# HU_revB.net
KiCad netlist of a schematic drawn in Altium Designer
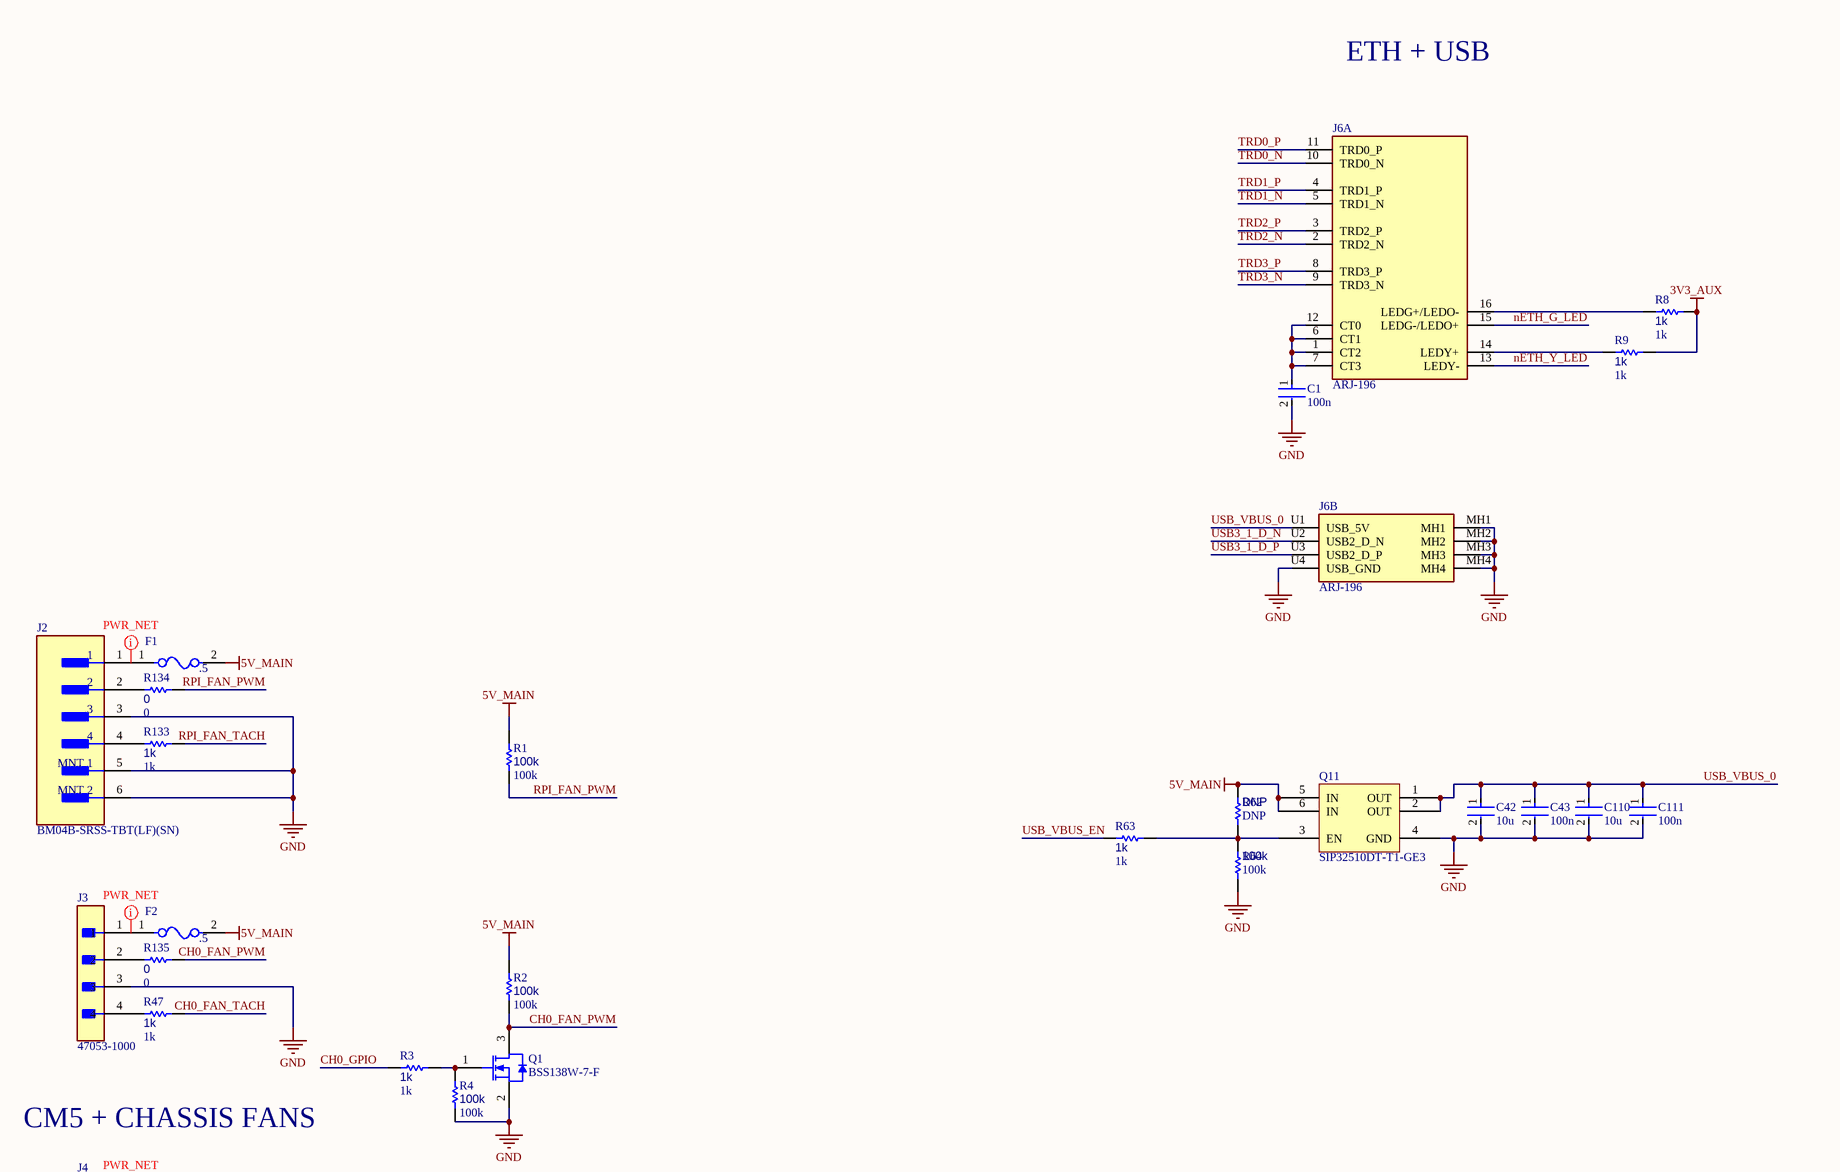
[diagram p0: HU_revB.SchDoc, top right]
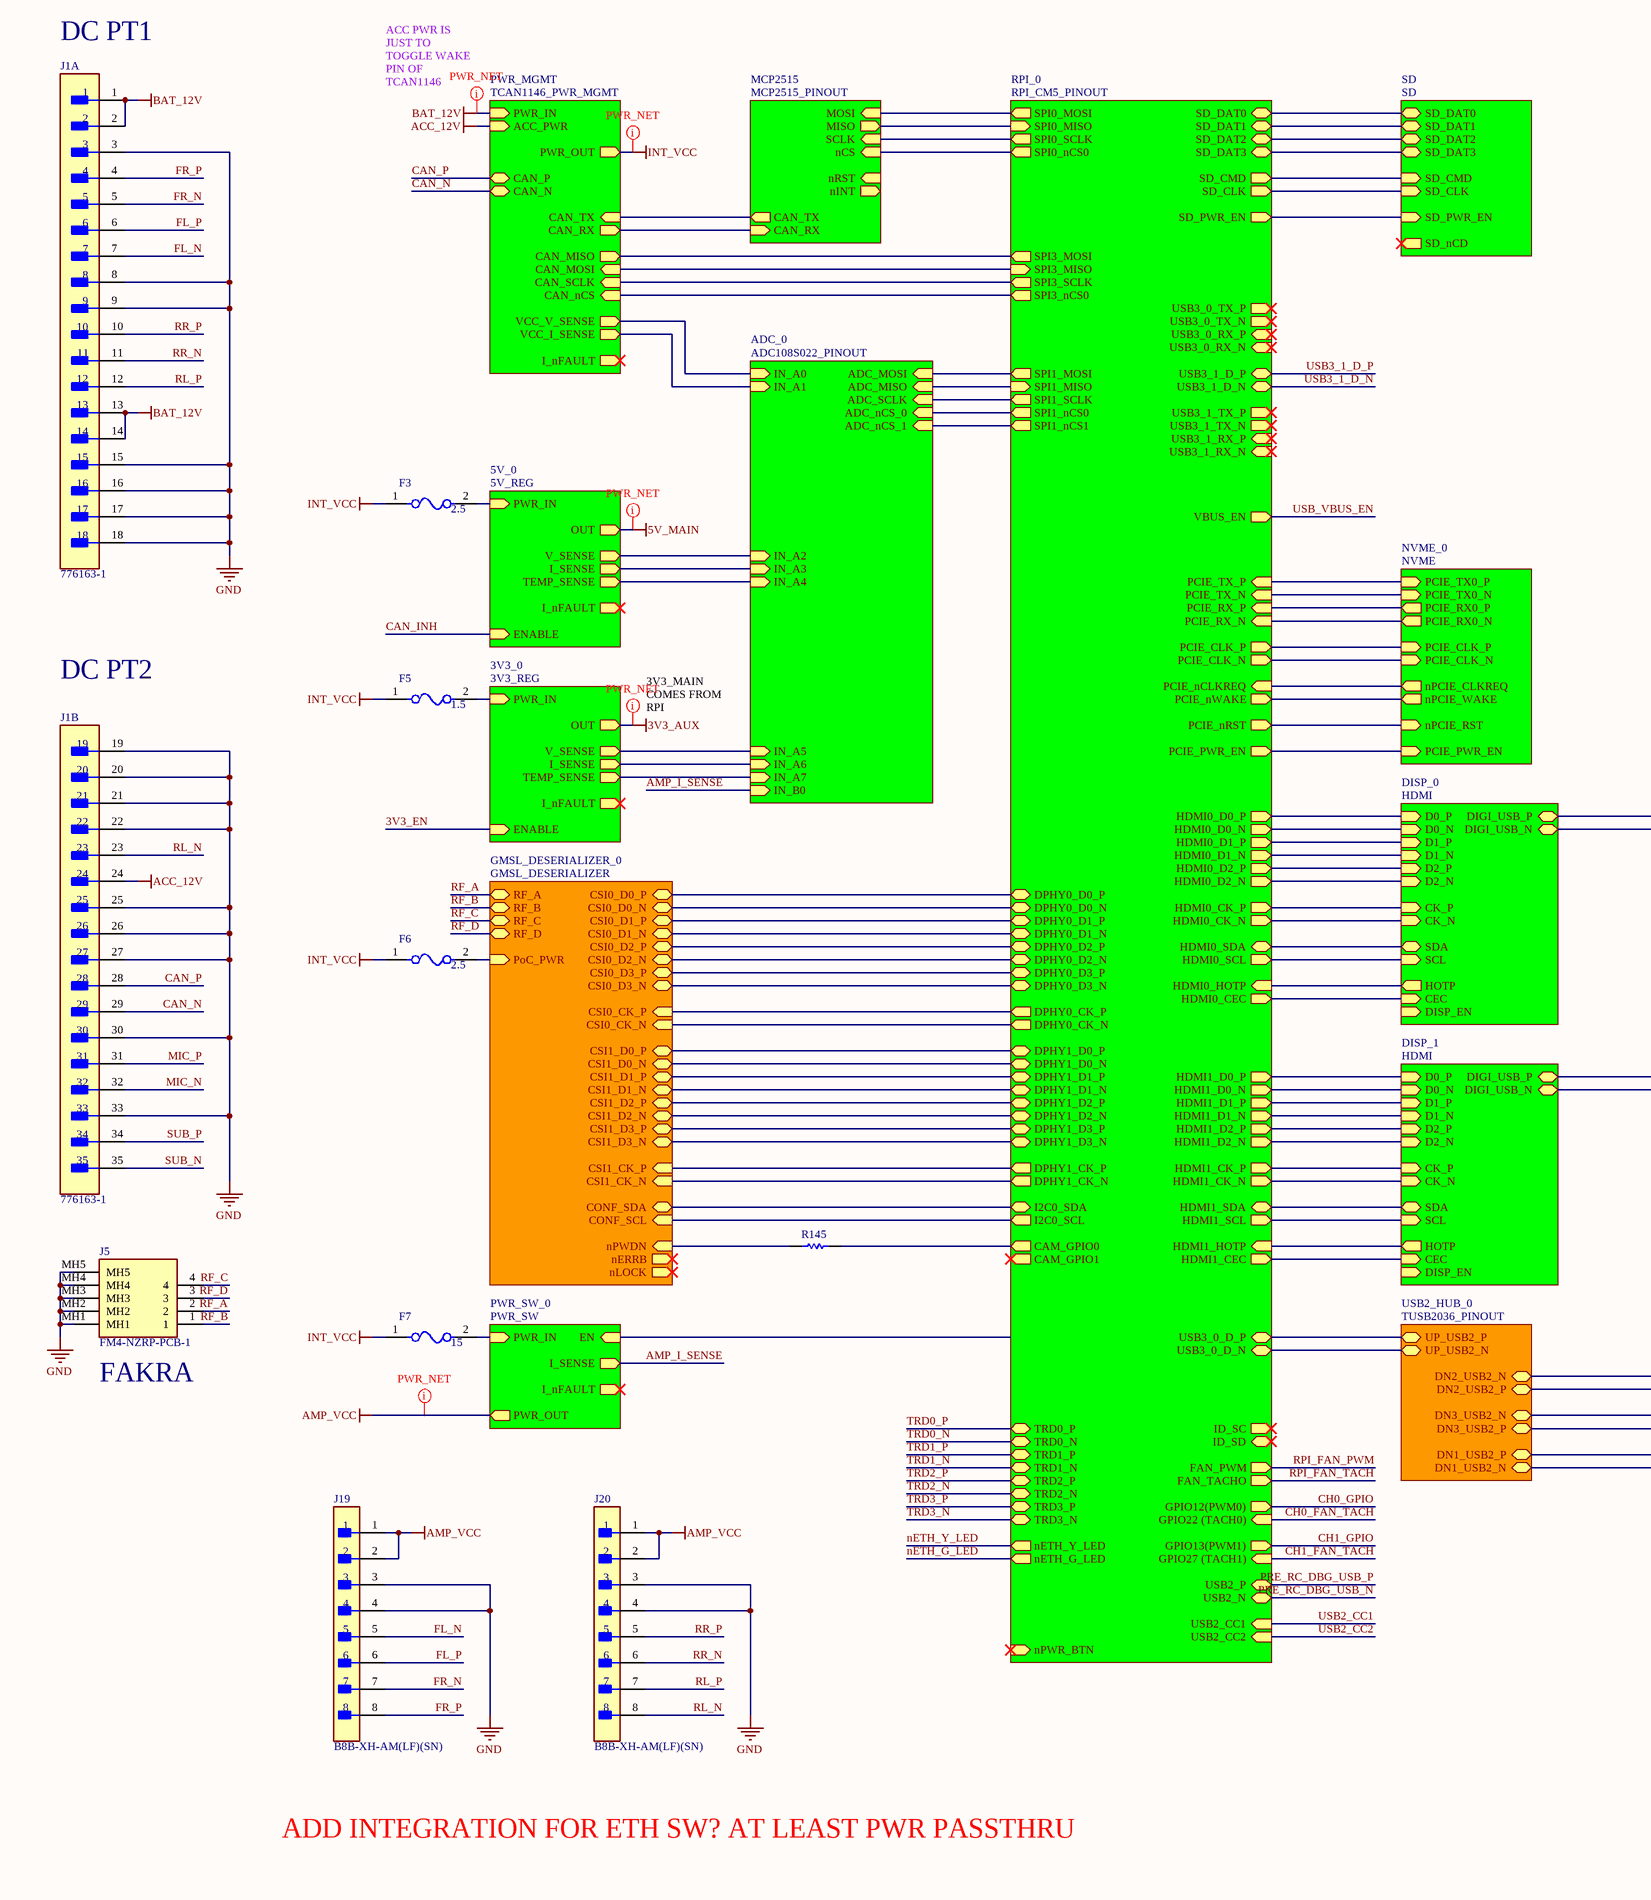
[diagram p1: HU_revB.SchDoc, bottom left]
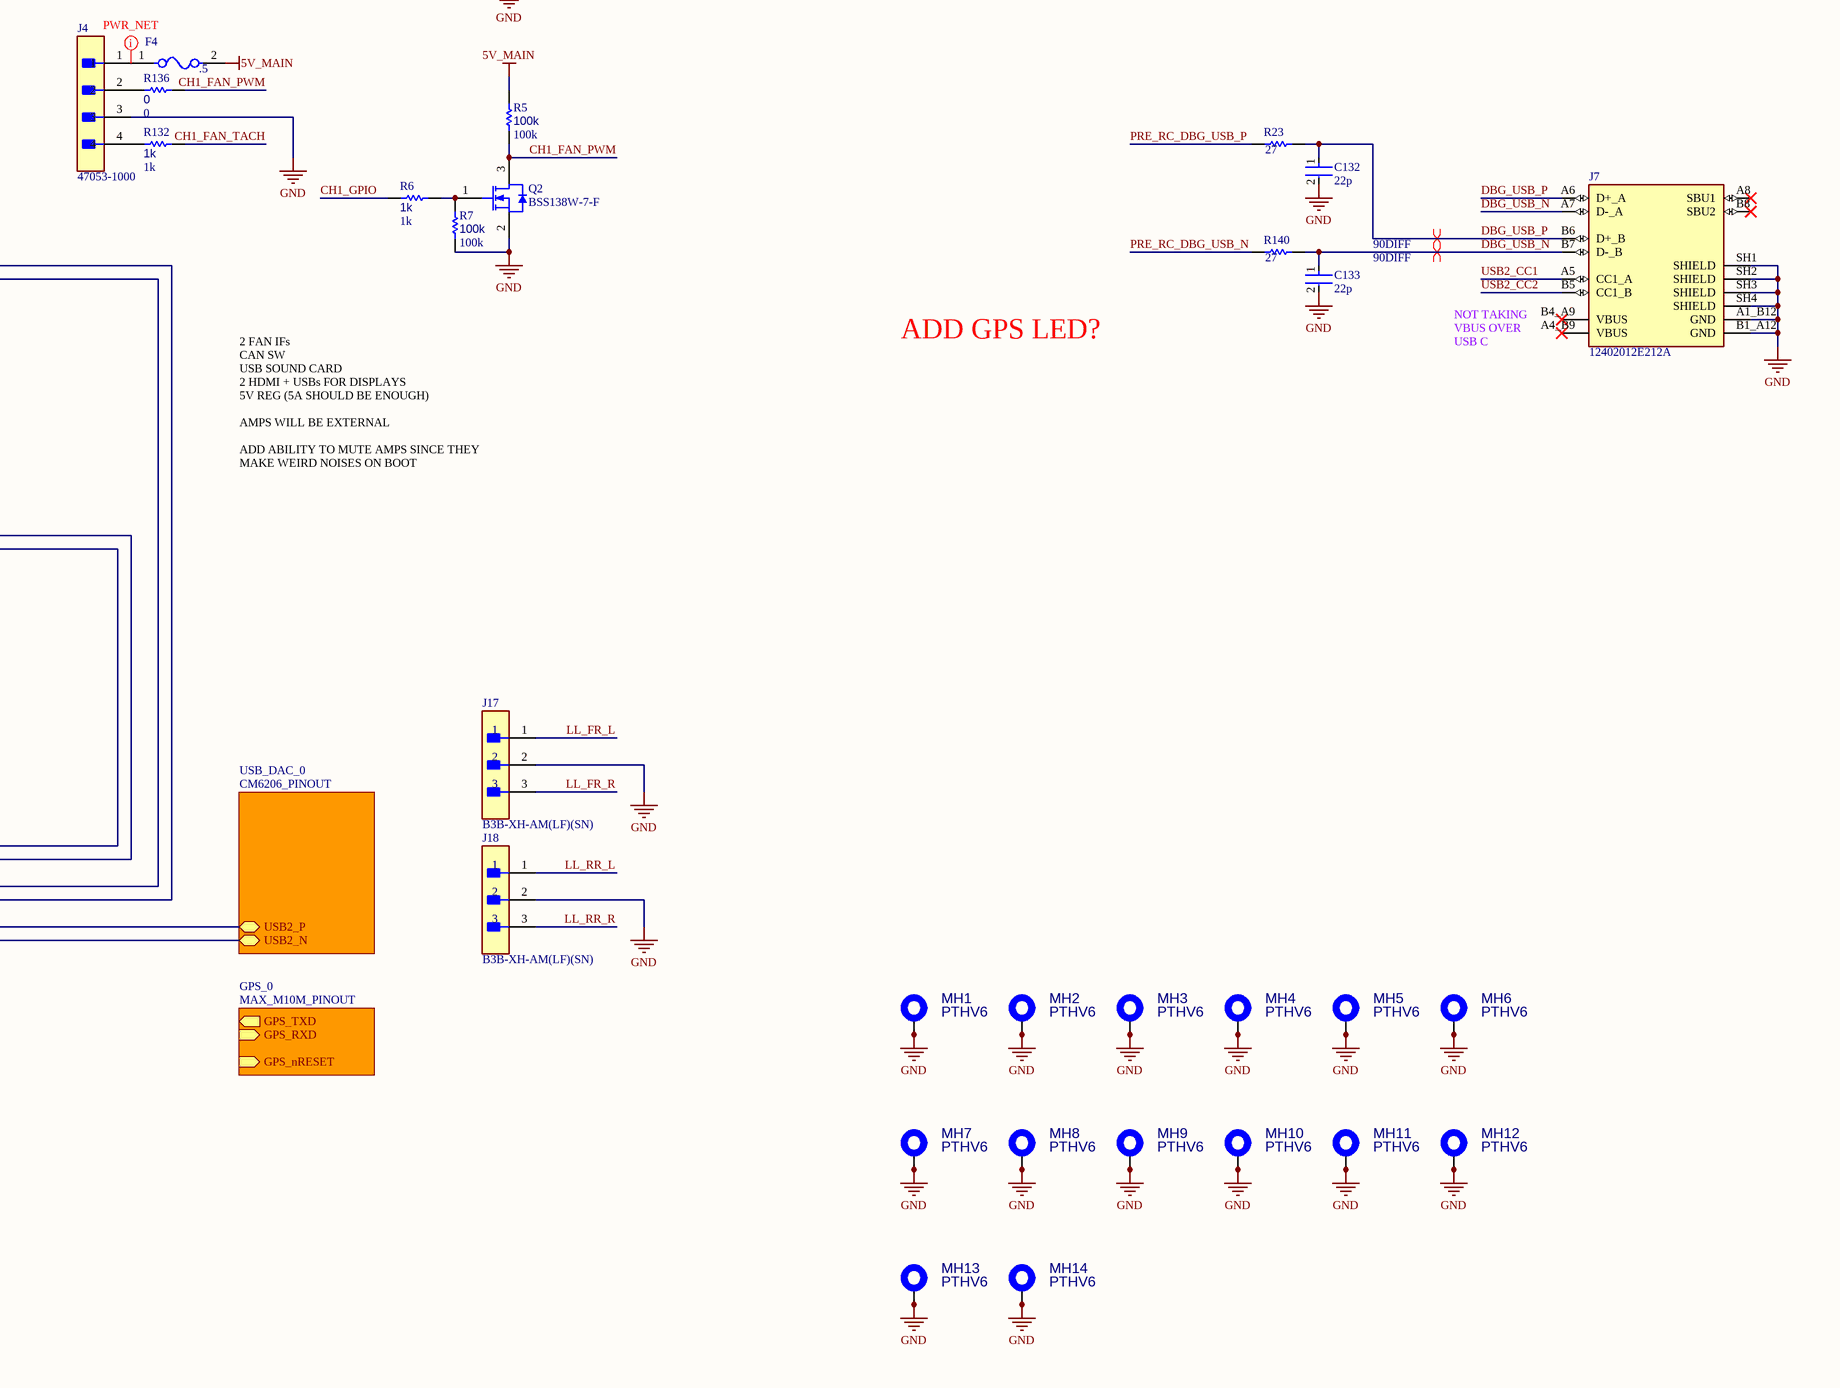
[diagram p2: HU_revB.SchDoc, bottom right]

(export (version "E")
  (design (tool "Eeschema 10.0.6"))
  (components
    (comp (ref "C1")
      (value "100n")
      (footprint "FP-0402-L_1_0_0_05-W_0_5-IPC_A")
      (description "LARGE PADS, 0402 CAP, CHANGE COMMENT TO MATCH REAL P/N")
      (libsource (lib "Space Concordia") (part "b4654b650e69147ec39a6b967a45e02"))
    )
    (comp (ref "C42")
      (value "10u")
      (footprint "FP-0402-L_1_0_0_05-W_0_5-IPC_A")
      (description "LARGE PADS, 0402 CAP, CHANGE COMMENT TO MATCH REAL P/N")
      (libsource (lib "Space Concordia") (part "b4654b650e69147ec39a6b967a45e02"))
    )
    (comp (ref "C43")
      (value "100n")
      (footprint "FP-0402-L_1_0_0_05-W_0_5-IPC_A")
      (description "LARGE PADS, 0402 CAP, CHANGE COMMENT TO MATCH REAL P/N")
      (libsource (lib "Space Concordia") (part "b4654b650e69147ec39a6b967a45e02"))
    )
    (comp (ref "C110")
      (value "10u")
      (footprint "FP-0402-L_1_0_0_05-W_0_5-IPC_A")
      (description "LARGE PADS, 0402 CAP, CHANGE COMMENT TO MATCH REAL P/N")
      (libsource (lib "Space Concordia") (part "b4654b650e69147ec39a6b967a45e02"))
    )
    (comp (ref "C111")
      (value "100n")
      (footprint "FP-0402-L_1_0_0_05-W_0_5-IPC_A")
      (description "LARGE PADS, 0402 CAP, CHANGE COMMENT TO MATCH REAL P/N")
      (libsource (lib "Space Concordia") (part "b4654b650e69147ec39a6b967a45e02"))
    )
    (comp (ref "C132")
      (value "22p")
      (footprint "FP-0402-L_1_0_0_05-W_0_5-IPC_A")
      (description "LARGE PADS, 0402 CAP, CHANGE COMMENT TO MATCH REAL P/N")
      (libsource (lib "Space Concordia") (part "b4654b650e69147ec39a6b967a45e02"))
    )
    (comp (ref "C133")
      (value "22p")
      (footprint "FP-0402-L_1_0_0_05-W_0_5-IPC_A")
      (description "LARGE PADS, 0402 CAP, CHANGE COMMENT TO MATCH REAL P/N")
      (libsource (lib "Space Concordia") (part "b4654b650e69147ec39a6b967a45e02"))
    )
    (comp (ref "F1")
      (value ".5")
      (footprint "FP-0685T-MFG")
      (description "FUSE BOARD MNT 5A 63VAC/VDC 1206")
      (libsource (lib "Altium Content Vault") (part "5bcf9b9f640e542cf0359d10258e979"))
    )
    (comp (ref "F2")
      (value ".5")
      (footprint "FP-0685T-MFG")
      (description "FUSE BOARD MNT 5A 63VAC/VDC 1206")
      (libsource (lib "Altium Content Vault") (part "5bcf9b9f640e542cf0359d10258e979"))
    )
    (comp (ref "F3")
      (value "2.5")
      (footprint "FP-0685T-MFG")
      (description "FUSE BOARD MNT 5A 63VAC/VDC 1206")
      (libsource (lib "Altium Content Vault") (part "5bcf9b9f640e542cf0359d10258e979"))
    )
    (comp (ref "F4")
      (value ".5")
      (footprint "FP-0685T-MFG")
      (description "FUSE BOARD MNT 5A 63VAC/VDC 1206")
      (libsource (lib "Altium Content Vault") (part "5bcf9b9f640e542cf0359d10258e979"))
    )
    (comp (ref "F5")
      (value "1.5")
      (footprint "FP-0685T-MFG")
      (description "FUSE BOARD MNT 5A 63VAC/VDC 1206")
      (libsource (lib "Altium Content Vault") (part "5bcf9b9f640e542cf0359d10258e979"))
    )
    (comp (ref "F6")
      (value "2.5")
      (footprint "FP-0685T-MFG")
      (description "FUSE BOARD MNT 5A 63VAC/VDC 1206")
      (libsource (lib "Altium Content Vault") (part "5bcf9b9f640e542cf0359d10258e979"))
    )
    (comp (ref "F7")
      (value "15")
      (footprint "FP-0685T-MFG")
      (description "FUSE BOARD MNT 5A 63VAC/VDC 1206")
      (libsource (lib "Altium Content Vault") (part "5bcf9b9f640e542cf0359d10258e979"))
    )
    (comp (ref "J1")
      (value "776163-1")
      (footprint "FP-776163-1-MFG")
      (description "CONN HEADER R/A 35POS 4MM")
      (libsource (lib "Altium Content Vault") (part "519b18991870a11d3ebcd8ad3c0113e"))
    )
    (comp (ref "J2")
      (value "BM04B-SRSS-TBT(LF)(SN)")
      (footprint "FP-BM04B-SRSS-TBT_LF_SN-MFG")
      (description "CONN HEADER SMD 4POS 1MM")
      (libsource (lib "Altium Content Vault") (part "8e3688c4b118bffc0dd9b7401e414ba"))
    )
    (comp (ref "J3")
      (value "47053-1000")
      (footprint "FP-470531000-MFG")
      (description "CONN HEADER VERT 4POS 2.54MM")
      (libsource (lib "Altium Content Vault") (part "299a8cea1bdcbc3624fe62c390fa72c"))
    )
    (comp (ref "J4")
      (value "47053-1000")
      (footprint "FP-470531000-MFG")
      (description "CONN HEADER VERT 4POS 2.54MM")
      (libsource (lib "Altium Content Vault") (part "299a8cea1bdcbc3624fe62c390fa72c"))
    )
    (comp (ref "J5")
      (value "FM4-NZRP-PCB-1")
      (footprint "FM4-NZRP-PCB-1-Footprint-1")
      (description "Connector RF Mini-FAKRA Plug 9GHz 50Ohm Solder Right Angle Through Hole")
      (libsource (lib "Space Concordia") (part "CMP-002-00085-1"))
    )
    (comp (ref "J6")
      (value "ARJ-196")
      (footprint "ARJ-196-Footprint-1")
      (description "Modular Connectors / Ethernet Connectors CONN MAGJACK 1PORT 1000 BASE-T")
      (libsource (lib "Space Concordia") (part "ARJ-196"))
    )
    (comp (ref "J7")
      (value "12402012E212A")
      (footprint "12402012E212A-Footprint-1")
      (description "USB Connector, USB Type C, USB 2.0, Receptacle, 24 Ways, Surface Mount, Through Hole Mount")
      (libsource (lib "Space Concordia") (part "12402012E212A"))
    )
    (comp (ref "J17")
      (value "B3B-XH-AM(LF)(SN)")
      (footprint "FP-B3B-XH-AM_LF_SN-MFG")
      (description "CONN HEADER VERT 3POS 2.5MM")
      (libsource (lib "Altium Content Vault") (part "0d3f023dd272f625e17a2be33dea85f"))
    )
    (comp (ref "J18")
      (value "B3B-XH-AM(LF)(SN)")
      (footprint "FP-B3B-XH-AM_LF_SN-MFG")
      (description "CONN HEADER VERT 3POS 2.5MM")
      (libsource (lib "Altium Content Vault") (part "0d3f023dd272f625e17a2be33dea85f"))
    )
    (comp (ref "J19")
      (value "B8B-XH-AM(LF)(SN)")
      (footprint "FP-B8B-XH-AM_LF_SN-MFG")
      (description "CONN HEADER VERT 8POS 2.5MM")
      (libsource (lib "Altium Content Vault") (part "99ec2b232beb5d2356d4d77f6a047f0"))
    )
    (comp (ref "J20")
      (value "B8B-XH-AM(LF)(SN)")
      (footprint "FP-B8B-XH-AM_LF_SN-MFG")
      (description "CONN HEADER VERT 8POS 2.5MM")
      (libsource (lib "Altium Content Vault") (part "99ec2b232beb5d2356d4d77f6a047f0"))
    )
    (comp (ref "MH1")
      (value "PTHV6")
      (footprint "PTHV6 M2")
      (libsource (lib "Space Concordia") (part "PTHV6"))
    )
    (comp (ref "MH2")
      (value "PTHV6")
      (footprint "PTHV6 M2")
      (libsource (lib "Space Concordia") (part "PTHV6"))
    )
    (comp (ref "MH3")
      (value "PTHV6")
      (footprint "PTHV6 M2")
      (libsource (lib "Space Concordia") (part "PTHV6"))
    )
    (comp (ref "MH4")
      (value "PTHV6")
      (footprint "PTHV6 M2")
      (libsource (lib "Space Concordia") (part "PTHV6"))
    )
    (comp (ref "MH5")
      (value "PTHV6")
      (footprint "PTHV6 M2")
      (libsource (lib "Space Concordia") (part "PTHV6"))
    )
    (comp (ref "MH6")
      (value "PTHV6")
      (footprint "PTHV6 M2")
      (libsource (lib "Space Concordia") (part "PTHV6"))
    )
    (comp (ref "MH7")
      (value "PTHV6")
      (footprint "PTHV6 M2")
      (libsource (lib "Space Concordia") (part "PTHV6"))
    )
    (comp (ref "MH8")
      (value "PTHV6")
      (footprint "PTHV6 M2")
      (libsource (lib "Space Concordia") (part "PTHV6"))
    )
    (comp (ref "MH9")
      (value "PTHV6")
      (footprint "PTHV6 M2")
      (libsource (lib "Space Concordia") (part "PTHV6"))
    )
    (comp (ref "MH10")
      (value "PTHV6")
      (footprint "PTHV6 M2")
      (libsource (lib "Space Concordia") (part "PTHV6"))
    )
    (comp (ref "MH11")
      (value "PTHV6")
      (footprint "PTHV6 M2")
      (libsource (lib "Space Concordia") (part "PTHV6"))
    )
    (comp (ref "MH12")
      (value "PTHV6")
      (footprint "PTHV6 M2")
      (libsource (lib "Space Concordia") (part "PTHV6"))
    )
    (comp (ref "MH13")
      (value "PTHV6")
      (footprint "PTHV6 M2")
      (libsource (lib "Space Concordia") (part "PTHV6"))
    )
    (comp (ref "MH14")
      (value "PTHV6")
      (footprint "PTHV6 M2")
      (libsource (lib "Space Concordia") (part "PTHV6"))
    )
    (comp (ref "Q1")
      (value "BSS138W-7-F")
      (footprint "DIOD-SOT323-3_V")
      (fields (field (name "MANUFACTURER") "DiodesIncorporated"))
      (libsource (lib "Altium Content Vault") (part "NEMOS-GSD-3"))
    )
    (comp (ref "Q2")
      (value "BSS138W-7-F")
      (footprint "DIOD-SOT323-3_V")
      (fields (field (name "MANUFACTURER") "DiodesIncorporated"))
      (libsource (lib "Altium Content Vault") (part "NEMOS-GSD-3"))
    )
    (comp (ref "Q11")
      (value "SIP32510DT-T1-GE3")
      (footprint "SOT95P284X110-6N")
      (description "Power Switch ICs – Power Distribution; VISHAY; SIP32510DT-T1-GE3; 1; 1; 5.5 V; SOT-23-6")
      (libsource (lib "Space Concordia") (part "SIP32510DT-T1-GE3"))
    )
    (comp (ref "R1")
      (value "100k")
      (footprint "R0603B")
      (description "Resistor")
      (fields (field (name "ALTIUM_VALUE") "100k"))
      (libsource (lib "Space Concordia") (part "Resistor"))
    )
    (comp (ref "R2")
      (value "100k")
      (footprint "R0603B")
      (description "Resistor")
      (fields (field (name "ALTIUM_VALUE") "100k"))
      (libsource (lib "Space Concordia") (part "Resistor"))
    )
    (comp (ref "R3")
      (value "1k")
      (footprint "R0603B")
      (description "Resistor")
      (fields (field (name "ALTIUM_VALUE") "1k"))
      (libsource (lib "Space Concordia") (part "Resistor"))
    )
    (comp (ref "R4")
      (value "100k")
      (footprint "R0603B")
      (description "Resistor")
      (fields (field (name "ALTIUM_VALUE") "100k"))
      (libsource (lib "Space Concordia") (part "Resistor"))
    )
    (comp (ref "R5")
      (value "100k")
      (footprint "R0603B")
      (description "Resistor")
      (fields (field (name "ALTIUM_VALUE") "100k"))
      (libsource (lib "Space Concordia") (part "Resistor"))
    )
    (comp (ref "R6")
      (value "1k")
      (footprint "R0603B")
      (description "Resistor")
      (fields (field (name "ALTIUM_VALUE") "1k"))
      (libsource (lib "Space Concordia") (part "Resistor"))
    )
    (comp (ref "R7")
      (value "100k")
      (footprint "R0603B")
      (description "Resistor")
      (fields (field (name "ALTIUM_VALUE") "100k"))
      (libsource (lib "Space Concordia") (part "Resistor"))
    )
    (comp (ref "R8")
      (value "1k")
      (footprint "R0603B")
      (description "Resistor")
      (fields (field (name "ALTIUM_VALUE") "1k"))
      (libsource (lib "Space Concordia") (part "Resistor"))
    )
    (comp (ref "R9")
      (value "1k")
      (footprint "R0603B")
      (description "Resistor")
      (fields (field (name "ALTIUM_VALUE") "1k"))
      (libsource (lib "Space Concordia") (part "Resistor"))
    )
    (comp (ref "R23")
      (value "27")
      (footprint "R0603B")
      (description "Resistor")
      (libsource (lib "Space Concordia") (part "Resistor"))
    )
    (comp (ref "R47")
      (value "1k")
      (footprint "R0603B")
      (description "Resistor")
      (fields (field (name "ALTIUM_VALUE") "1k"))
      (libsource (lib "Space Concordia") (part "Resistor"))
    )
    (comp (ref "R62")
      (value "DNP")
      (footprint "R0603B")
      (description "Resistor")
      (fields (field (name "ALTIUM_VALUE") "DNP"))
      (libsource (lib "Space Concordia") (part "Resistor"))
    )
    (comp (ref "R63")
      (value "1k")
      (footprint "R0603B")
      (description "Resistor")
      (fields (field (name "ALTIUM_VALUE") "1k"))
      (libsource (lib "Space Concordia") (part "Resistor"))
    )
    (comp (ref "R64")
      (value "100k")
      (footprint "R0603B")
      (description "Resistor")
      (fields (field (name "ALTIUM_VALUE") "100k"))
      (libsource (lib "Space Concordia") (part "Resistor"))
    )
    (comp (ref "R132")
      (value "1k")
      (footprint "R0603B")
      (description "Resistor")
      (fields (field (name "ALTIUM_VALUE") "1k"))
      (libsource (lib "Space Concordia") (part "Resistor"))
    )
    (comp (ref "R133")
      (value "1k")
      (footprint "R0603B")
      (description "Resistor")
      (fields (field (name "ALTIUM_VALUE") "1k"))
      (libsource (lib "Space Concordia") (part "Resistor"))
    )
    (comp (ref "R134")
      (value "0")
      (footprint "R0603B")
      (description "Resistor")
      (fields (field (name "ALTIUM_VALUE") "0"))
      (libsource (lib "Space Concordia") (part "Resistor"))
    )
    (comp (ref "R135")
      (value "0")
      (footprint "R0603B")
      (description "Resistor")
      (fields (field (name "ALTIUM_VALUE") "0"))
      (libsource (lib "Space Concordia") (part "Resistor"))
    )
    (comp (ref "R136")
      (value "0")
      (footprint "R0603B")
      (description "Resistor")
      (fields (field (name "ALTIUM_VALUE") "0"))
      (libsource (lib "Space Concordia") (part "Resistor"))
    )
    (comp (ref "R140")
      (value "27")
      (footprint "R0603B")
      (description "Resistor")
      (libsource (lib "Space Concordia") (part "Resistor"))
    )
    (comp (ref "R145")
      (value "DNP")
      (footprint "RESC1005X40X25ML05T05")
      (description "READ THE NAME")
      (libsource (lib "Space Concordia") (part "CMP-009-00206-2"))
    )
  )
  (nets
    (net (code "4") (name "/CAM_GPIO0") (class "Default")
      (node (ref "R145") (pin "1") (pinfunction "1_1") (pintype "passive"))
    )
    (net (code "9") (name "/CAN_N") (class "Default")
      (node (ref "J1") (pin "29") (pinfunction "29_29") (pintype "passive"))
    )
    (net (code "10") (name "/CAN_P") (class "Default")
      (node (ref "J1") (pin "28") (pinfunction "28_28") (pintype "passive"))
    )
    (net (code "13") (name "/CH0_FAN_PWM") (class "Default")
      (node (ref "Q1") (pin "3") (pinfunction "D_3") (pintype "passive"))
      (node (ref "R135") (pin "2") (pinfunction "2_2") (pintype "passive"))
      (node (ref "R2") (pin "2") (pinfunction "2_2") (pintype "passive"))
    )
    (net (code "14") (name "/CH0_FAN_TACH") (class "Default")
      (node (ref "R47") (pin "2") (pinfunction "2_2") (pintype "passive"))
    )
    (net (code "15") (name "/CH0_GPIO") (class "Default")
      (node (ref "R3") (pin "1") (pinfunction "1_1") (pintype "passive"))
    )
    (net (code "16") (name "/CH1_FAN_PWM") (class "Default")
      (node (ref "Q2") (pin "3") (pinfunction "D_3") (pintype "passive"))
      (node (ref "R136") (pin "2") (pinfunction "2_2") (pintype "passive"))
      (node (ref "R5") (pin "2") (pinfunction "2_2") (pintype "passive"))
    )
    (net (code "17") (name "/CH1_FAN_TACH") (class "Default")
      (node (ref "R132") (pin "2") (pinfunction "2_2") (pintype "passive"))
    )
    (net (code "18") (name "/CH1_GPIO") (class "Default")
      (node (ref "R6") (pin "1") (pinfunction "1_1") (pintype "passive"))
    )
    (net (code "36") (name "/DBG_USB_N") (class "Default")
      (node (ref "C133") (pin "1") (pinfunction "1_1") (pintype "passive"))
      (node (ref "J7") (pin "A7") (pinfunction "D-_A_A7") (pintype "bidirectional"))
      (node (ref "J7") (pin "B7") (pinfunction "D-_B_B7") (pintype "bidirectional"))
      (node (ref "R140") (pin "1") (pinfunction "1_1") (pintype "passive"))
    )
    (net (code "37") (name "/DBG_USB_P") (class "Default")
      (node (ref "C132") (pin "1") (pinfunction "1_1") (pintype "passive"))
      (node (ref "J7") (pin "A6") (pinfunction "D+_A_A6") (pintype "bidirectional"))
      (node (ref "J7") (pin "B6") (pinfunction "D+_B_B6") (pintype "bidirectional"))
      (node (ref "R23") (pin "1") (pinfunction "1_1") (pintype "passive"))
    )
    (net (code "51") (name "/FL_N") (class "Default")
      (node (ref "J1") (pin "7") (pinfunction "7_7") (pintype "passive"))
      (node (ref "J19") (pin "5") (pinfunction "5_5") (pintype "passive"))
    )
    (net (code "52") (name "/FL_P") (class "Default")
      (node (ref "J1") (pin "6") (pinfunction "6_6") (pintype "passive"))
      (node (ref "J19") (pin "6") (pinfunction "6_6") (pintype "passive"))
    )
    (net (code "53") (name "/FR_N") (class "Default")
      (node (ref "J1") (pin "5") (pinfunction "5_5") (pintype "passive"))
      (node (ref "J19") (pin "7") (pinfunction "7_7") (pintype "passive"))
    )
    (net (code "54") (name "/FR_P") (class "Default")
      (node (ref "J1") (pin "4") (pinfunction "4_4") (pintype "passive"))
      (node (ref "J19") (pin "8") (pinfunction "8_8") (pintype "passive"))
    )
    (net (code "91") (name "/LL_FR_L") (class "Default")
      (node (ref "J17") (pin "1") (pinfunction "1_1") (pintype "passive"))
    )
    (net (code "92") (name "/LL_FR_R") (class "Default")
      (node (ref "J17") (pin "3") (pinfunction "3_3") (pintype "passive"))
    )
    (net (code "93") (name "/LL_RR_L") (class "Default")
      (node (ref "J18") (pin "1") (pinfunction "1_1") (pintype "passive"))
    )
    (net (code "94") (name "/LL_RR_R") (class "Default")
      (node (ref "J18") (pin "3") (pinfunction "3_3") (pintype "passive"))
    )
    (net (code "95") (name "/MIC_N") (class "Default")
      (node (ref "J1") (pin "32") (pinfunction "32_32") (pintype "passive"))
    )
    (net (code "96") (name "/MIC_P") (class "Default")
      (node (ref "J1") (pin "31") (pinfunction "31_31") (pintype "passive"))
    )
    (net (code "107") (name "/PRE_RC_DBG_USB_N") (class "Default")
      (node (ref "R140") (pin "2") (pinfunction "2_2") (pintype "passive"))
    )
    (net (code "108") (name "/PRE_RC_DBG_USB_P") (class "Default")
      (node (ref "R23") (pin "2") (pinfunction "2_2") (pintype "passive"))
    )
    (net (code "109") (name "/PWR_IN") (class "Default")
      (node (ref "F7") (pin "2") (pinfunction "2_2") (pintype "passive"))
    )
    (net (code "110") (name "/PWR_IN_1") (class "Default")
      (node (ref "F3") (pin "2") (pinfunction "2_2") (pintype "passive"))
    )
    (net (code "111") (name "/PWR_IN_2") (class "Default")
      (node (ref "F5") (pin "2") (pinfunction "2_2") (pintype "passive"))
    )
    (net (code "112") (name "/PoC_PWR") (class "Default")
      (node (ref "F6") (pin "2") (pinfunction "2_2") (pintype "passive"))
    )
    (net (code "113") (name "/RF_A") (class "Default")
      (node (ref "J5") (pin "2") (pinfunction "2_2") (pintype "passive"))
    )
    (net (code "114") (name "/RF_B") (class "Default")
      (node (ref "J5") (pin "1") (pinfunction "1_1") (pintype "passive"))
    )
    (net (code "115") (name "/RF_C") (class "Default")
      (node (ref "J5") (pin "4") (pinfunction "4_4") (pintype "passive"))
    )
    (net (code "116") (name "/RF_D") (class "Default")
      (node (ref "J5") (pin "3") (pinfunction "3_3") (pintype "passive"))
    )
    (net (code "117") (name "/RL_N") (class "Default")
      (node (ref "J1") (pin "23") (pinfunction "23_23") (pintype "passive"))
      (node (ref "J20") (pin "8") (pinfunction "8_8") (pintype "passive"))
    )
    (net (code "118") (name "/RL_P") (class "Default")
      (node (ref "J1") (pin "12") (pinfunction "12_12") (pintype "passive"))
      (node (ref "J20") (pin "7") (pinfunction "7_7") (pintype "passive"))
    )
    (net (code "119") (name "/RPI_FAN_PWM") (class "Default")
      (node (ref "R1") (pin "2") (pinfunction "2_2") (pintype "passive"))
      (node (ref "R134") (pin "2") (pinfunction "2_2") (pintype "passive"))
    )
    (net (code "120") (name "/RPI_FAN_TACH") (class "Default")
      (node (ref "R133") (pin "2") (pinfunction "2_2") (pintype "passive"))
    )
    (net (code "121") (name "/RR_N") (class "Default")
      (node (ref "J1") (pin "11") (pinfunction "11_11") (pintype "passive"))
      (node (ref "J20") (pin "6") (pinfunction "6_6") (pintype "passive"))
    )
    (net (code "122") (name "/RR_P") (class "Default")
      (node (ref "J1") (pin "10") (pinfunction "10_10") (pintype "passive"))
      (node (ref "J20") (pin "5") (pinfunction "5_5") (pintype "passive"))
    )
    (net (code "140") (name "/SUB_N") (class "Default")
      (node (ref "J1") (pin "35") (pinfunction "35_35") (pintype "passive"))
    )
    (net (code "141") (name "/SUB_P") (class "Default")
      (node (ref "J1") (pin "34") (pinfunction "34_34") (pintype "passive"))
    )
    (net (code "144") (name "/TRD0_N") (class "Default")
      (node (ref "J6") (pin "10") (pinfunction "TRD0_N_10") (pintype "passive"))
    )
    (net (code "145") (name "/TRD0_P") (class "Default")
      (node (ref "J6") (pin "11") (pinfunction "TRD0_P_11") (pintype "passive"))
    )
    (net (code "146") (name "/TRD1_N") (class "Default")
      (node (ref "J6") (pin "5") (pinfunction "TRD1_N_5") (pintype "passive"))
    )
    (net (code "147") (name "/TRD1_P") (class "Default")
      (node (ref "J6") (pin "4") (pinfunction "TRD1_P_4") (pintype "passive"))
    )
    (net (code "148") (name "/TRD2_N") (class "Default")
      (node (ref "J6") (pin "2") (pinfunction "TRD2_N_2") (pintype "passive"))
    )
    (net (code "149") (name "/TRD2_P") (class "Default")
      (node (ref "J6") (pin "3") (pinfunction "TRD2_P_3") (pintype "passive"))
    )
    (net (code "150") (name "/TRD3_N") (class "Default")
      (node (ref "J6") (pin "9") (pinfunction "TRD3_N_9") (pintype "passive"))
    )
    (net (code "151") (name "/TRD3_P") (class "Default")
      (node (ref "J6") (pin "8") (pinfunction "TRD3_P_8") (pintype "passive"))
    )
    (net (code "154") (name "/USB2_CC1") (class "Default")
      (node (ref "J7") (pin "A5") (pinfunction "CC1_A_A5") (pintype "bidirectional"))
    )
    (net (code "155") (name "/USB2_CC2") (class "Default")
      (node (ref "J7") (pin "B5") (pinfunction "CC1_B_B5") (pintype "bidirectional"))
    )
    (net (code "160") (name "/USB3_1_D_N") (class "Default")
      (node (ref "J6") (pin "U2") (pinfunction "USB2_D_N_U2") (pintype "passive"))
    )
    (net (code "161") (name "/USB3_1_D_P") (class "Default")
      (node (ref "J6") (pin "U3") (pinfunction "USB2_D_P_U3") (pintype "passive"))
    )
    (net (code "166") (name "/USB_VBUS_0") (class "Default")
      (node (ref "C110") (pin "1") (pinfunction "1_1") (pintype "passive"))
      (node (ref "C111") (pin "1") (pinfunction "1_1") (pintype "passive"))
      (node (ref "C42") (pin "1") (pinfunction "1_1") (pintype "passive"))
      (node (ref "C43") (pin "1") (pinfunction "1_1") (pintype "passive"))
      (node (ref "J6") (pin "U1") (pinfunction "USB_5V_U1") (pintype "passive"))
      (node (ref "Q11") (pin "1") (pinfunction "OUT_1") (pintype "passive"))
      (node (ref "Q11") (pin "2") (pinfunction "OUT_2") (pintype "passive"))
    )
    (net (code "167") (name "/USB_VBUS_EN") (class "Default")
      (node (ref "R63") (pin "2") (pinfunction "2_2") (pintype "passive"))
    )
    (net (code "173") (name "/nETH_G_LED") (class "Default")
      (node (ref "J6") (pin "15") (pinfunction "LEDG-/LEDO+_15") (pintype "passive"))
    )
    (net (code "174") (name "/nETH_Y_LED") (class "Default")
      (node (ref "J6") (pin "13") (pinfunction "LEDY-_13") (pintype "passive"))
    )
    (net (code "178") (name "/nPWDN") (class "Default")
      (node (ref "R145") (pin "2") (pinfunction "2_2") (pintype "passive"))
    )
    (net (code "181") (name "3V3_AUX") (class "Default")
      (node (ref "R8") (pin "1") (pinfunction "1_1") (pintype "passive"))
      (node (ref "R9") (pin "1") (pinfunction "1_1") (pintype "passive"))
    )
    (net (code "182") (name "5V_MAIN") (class "Default")
      (node (ref "F1") (pin "2") (pinfunction "2_2") (pintype "passive"))
      (node (ref "F2") (pin "2") (pinfunction "2_2") (pintype "passive"))
      (node (ref "F4") (pin "2") (pinfunction "2_2") (pintype "passive"))
      (node (ref "Q11") (pin "5") (pinfunction "IN_5") (pintype "passive"))
      (node (ref "Q11") (pin "6") (pinfunction "IN_6") (pintype "passive"))
      (node (ref "R1") (pin "1") (pinfunction "1_1") (pintype "passive"))
      (node (ref "R2") (pin "1") (pinfunction "1_1") (pintype "passive"))
      (node (ref "R5") (pin "1") (pinfunction "1_1") (pintype "passive"))
      (node (ref "R62") (pin "2") (pinfunction "2_2") (pintype "passive"))
    )
    (net (code "183") (name "ACC_12V") (class "Default")
      (node (ref "J1") (pin "24") (pinfunction "24_24") (pintype "passive"))
    )
    (net (code "184") (name "AMP_VCC") (class "Default")
      (node (ref "J19") (pin "1") (pinfunction "1_1") (pintype "passive"))
      (node (ref "J19") (pin "2") (pinfunction "2_2") (pintype "passive"))
      (node (ref "J20") (pin "1") (pinfunction "1_1") (pintype "passive"))
      (node (ref "J20") (pin "2") (pinfunction "2_2") (pintype "passive"))
    )
    (net (code "185") (name "BAT_12V") (class "Default")
      (node (ref "J1") (pin "1") (pinfunction "1_1") (pintype "passive"))
      (node (ref "J1") (pin "13") (pinfunction "13_13") (pintype "passive"))
      (node (ref "J1") (pin "14") (pinfunction "14_14") (pintype "passive"))
      (node (ref "J1") (pin "2") (pinfunction "2_2") (pintype "passive"))
    )
    (net (code "186") (name "GND") (class "Default")
      (node (ref "C1") (pin "2") (pinfunction "2_2") (pintype "passive"))
      (node (ref "C110") (pin "2") (pinfunction "2_2") (pintype "passive"))
      (node (ref "C111") (pin "2") (pinfunction "2_2") (pintype "passive"))
      (node (ref "C132") (pin "2") (pinfunction "2_2") (pintype "passive"))
      (node (ref "C133") (pin "2") (pinfunction "2_2") (pintype "passive"))
      (node (ref "C42") (pin "2") (pinfunction "2_2") (pintype "passive"))
      (node (ref "C43") (pin "2") (pinfunction "2_2") (pintype "passive"))
      (node (ref "J1") (pin "15") (pinfunction "15_15") (pintype "passive"))
      (node (ref "J1") (pin "16") (pinfunction "16_16") (pintype "passive"))
      (node (ref "J1") (pin "17") (pinfunction "17_17") (pintype "passive"))
      (node (ref "J1") (pin "18") (pinfunction "18_18") (pintype "passive"))
      (node (ref "J1") (pin "19") (pinfunction "19_19") (pintype "passive"))
      (node (ref "J1") (pin "20") (pinfunction "20_20") (pintype "passive"))
      (node (ref "J1") (pin "21") (pinfunction "21_21") (pintype "passive"))
      (node (ref "J1") (pin "22") (pinfunction "22_22") (pintype "passive"))
      (node (ref "J1") (pin "25") (pinfunction "25_25") (pintype "passive"))
      (node (ref "J1") (pin "26") (pinfunction "26_26") (pintype "passive"))
      (node (ref "J1") (pin "27") (pinfunction "27_27") (pintype "passive"))
      (node (ref "J1") (pin "3") (pinfunction "3_3") (pintype "passive"))
      (node (ref "J1") (pin "30") (pinfunction "30_30") (pintype "passive"))
      (node (ref "J1") (pin "33") (pinfunction "33_33") (pintype "passive"))
      (node (ref "J1") (pin "8") (pinfunction "8_8") (pintype "passive"))
      (node (ref "J1") (pin "9") (pinfunction "9_9") (pintype "passive"))
      (node (ref "J17") (pin "2") (pinfunction "2_2") (pintype "passive"))
      (node (ref "J18") (pin "2") (pinfunction "2_2") (pintype "passive"))
      (node (ref "J19") (pin "3") (pinfunction "3_3") (pintype "passive"))
      (node (ref "J19") (pin "4") (pinfunction "4_4") (pintype "passive"))
      (node (ref "J2") (pin "3") (pinfunction "3_3") (pintype "passive"))
      (node (ref "J2") (pin "5") (pinfunction "MNT_1_5") (pintype "passive"))
      (node (ref "J2") (pin "6") (pinfunction "MNT_2_6") (pintype "passive"))
      (node (ref "J20") (pin "3") (pinfunction "3_3") (pintype "passive"))
      (node (ref "J20") (pin "4") (pinfunction "4_4") (pintype "passive"))
      (node (ref "J3") (pin "3") (pinfunction "3_3") (pintype "passive"))
      (node (ref "J4") (pin "3") (pinfunction "3_3") (pintype "passive"))
      (node (ref "J5") (pin "MH1") (pinfunction "MH1_MH1") (pintype "passive"))
      (node (ref "J5") (pin "MH2") (pinfunction "MH2_MH2") (pintype "passive"))
      (node (ref "J5") (pin "MH3") (pinfunction "MH3_MH3") (pintype "passive"))
      (node (ref "J5") (pin "MH4") (pinfunction "MH4_MH4") (pintype "passive"))
      (node (ref "J5") (pin "MH5") (pinfunction "MH5_MH5") (pintype "passive"))
      (node (ref "J6") (pin "MH1") (pinfunction "MH1_MH1") (pintype "passive"))
      (node (ref "J6") (pin "MH2") (pinfunction "MH2_MH2") (pintype "passive"))
      (node (ref "J6") (pin "MH3") (pinfunction "MH3_MH3") (pintype "passive"))
      (node (ref "J6") (pin "MH4") (pinfunction "MH4_MH4") (pintype "passive"))
      (node (ref "J6") (pin "U4") (pinfunction "USB_GND_U4") (pintype "passive"))
      (node (ref "J7") (pin "A1_B12") (pinfunction "GND_A1_B12") (pintype "power_in"))
      (node (ref "J7") (pin "B1_A12") (pinfunction "GND_B1_A12") (pintype "power_in"))
      (node (ref "J7") (pin "SH1") (pinfunction "SHIELD_SH1") (pintype "passive"))
      (node (ref "J7") (pin "SH2") (pinfunction "SHIELD_SH2") (pintype "passive"))
      (node (ref "J7") (pin "SH3") (pinfunction "SHIELD_SH3") (pintype "passive"))
      (node (ref "J7") (pin "SH4") (pinfunction "SHIELD_SH4") (pintype "passive"))
      (node (ref "MH1") (pin "1") (pinfunction "MH_1") (pintype "passive"))
      (node (ref "MH1") (pin "2") (pinfunction "V1_2") (pintype "passive"))
      (node (ref "MH1") (pin "3") (pinfunction "V2_3") (pintype "passive"))
      (node (ref "MH1") (pin "4") (pinfunction "V3_4") (pintype "passive"))
      (node (ref "MH1") (pin "5") (pinfunction "V4_5") (pintype "passive"))
      (node (ref "MH1") (pin "6") (pinfunction "V5_6") (pintype "passive"))
      (node (ref "MH1") (pin "7") (pinfunction "V6_7") (pintype "passive"))
      (node (ref "MH10") (pin "1") (pinfunction "MH_1") (pintype "passive"))
      (node (ref "MH10") (pin "2") (pinfunction "V1_2") (pintype "passive"))
      (node (ref "MH10") (pin "3") (pinfunction "V2_3") (pintype "passive"))
      (node (ref "MH10") (pin "4") (pinfunction "V3_4") (pintype "passive"))
      (node (ref "MH10") (pin "5") (pinfunction "V4_5") (pintype "passive"))
      (node (ref "MH10") (pin "6") (pinfunction "V5_6") (pintype "passive"))
      (node (ref "MH10") (pin "7") (pinfunction "V6_7") (pintype "passive"))
      (node (ref "MH11") (pin "1") (pinfunction "MH_1") (pintype "passive"))
      (node (ref "MH11") (pin "2") (pinfunction "V1_2") (pintype "passive"))
      (node (ref "MH11") (pin "3") (pinfunction "V2_3") (pintype "passive"))
      (node (ref "MH11") (pin "4") (pinfunction "V3_4") (pintype "passive"))
      (node (ref "MH11") (pin "5") (pinfunction "V4_5") (pintype "passive"))
      (node (ref "MH11") (pin "6") (pinfunction "V5_6") (pintype "passive"))
      (node (ref "MH11") (pin "7") (pinfunction "V6_7") (pintype "passive"))
      (node (ref "MH12") (pin "1") (pinfunction "MH_1") (pintype "passive"))
      (node (ref "MH12") (pin "2") (pinfunction "V1_2") (pintype "passive"))
      (node (ref "MH12") (pin "3") (pinfunction "V2_3") (pintype "passive"))
      (node (ref "MH12") (pin "4") (pinfunction "V3_4") (pintype "passive"))
      (node (ref "MH12") (pin "5") (pinfunction "V4_5") (pintype "passive"))
      (node (ref "MH12") (pin "6") (pinfunction "V5_6") (pintype "passive"))
      (node (ref "MH12") (pin "7") (pinfunction "V6_7") (pintype "passive"))
      (node (ref "MH13") (pin "1") (pinfunction "MH_1") (pintype "passive"))
      (node (ref "MH13") (pin "2") (pinfunction "V1_2") (pintype "passive"))
      (node (ref "MH13") (pin "3") (pinfunction "V2_3") (pintype "passive"))
      (node (ref "MH13") (pin "4") (pinfunction "V3_4") (pintype "passive"))
      (node (ref "MH13") (pin "5") (pinfunction "V4_5") (pintype "passive"))
      (node (ref "MH13") (pin "6") (pinfunction "V5_6") (pintype "passive"))
      (node (ref "MH13") (pin "7") (pinfunction "V6_7") (pintype "passive"))
      (node (ref "MH14") (pin "1") (pinfunction "MH_1") (pintype "passive"))
      (node (ref "MH14") (pin "2") (pinfunction "V1_2") (pintype "passive"))
      (node (ref "MH14") (pin "3") (pinfunction "V2_3") (pintype "passive"))
      (node (ref "MH14") (pin "4") (pinfunction "V3_4") (pintype "passive"))
      (node (ref "MH14") (pin "5") (pinfunction "V4_5") (pintype "passive"))
      (node (ref "MH14") (pin "6") (pinfunction "V5_6") (pintype "passive"))
      (node (ref "MH14") (pin "7") (pinfunction "V6_7") (pintype "passive"))
      (node (ref "MH2") (pin "1") (pinfunction "MH_1") (pintype "passive"))
      (node (ref "MH2") (pin "2") (pinfunction "V1_2") (pintype "passive"))
      (node (ref "MH2") (pin "3") (pinfunction "V2_3") (pintype "passive"))
      (node (ref "MH2") (pin "4") (pinfunction "V3_4") (pintype "passive"))
      (node (ref "MH2") (pin "5") (pinfunction "V4_5") (pintype "passive"))
      (node (ref "MH2") (pin "6") (pinfunction "V5_6") (pintype "passive"))
      (node (ref "MH2") (pin "7") (pinfunction "V6_7") (pintype "passive"))
      (node (ref "MH3") (pin "1") (pinfunction "MH_1") (pintype "passive"))
      (node (ref "MH3") (pin "2") (pinfunction "V1_2") (pintype "passive"))
      (node (ref "MH3") (pin "3") (pinfunction "V2_3") (pintype "passive"))
      (node (ref "MH3") (pin "4") (pinfunction "V3_4") (pintype "passive"))
      (node (ref "MH3") (pin "5") (pinfunction "V4_5") (pintype "passive"))
      (node (ref "MH3") (pin "6") (pinfunction "V5_6") (pintype "passive"))
      (node (ref "MH3") (pin "7") (pinfunction "V6_7") (pintype "passive"))
      (node (ref "MH4") (pin "1") (pinfunction "MH_1") (pintype "passive"))
      (node (ref "MH4") (pin "2") (pinfunction "V1_2") (pintype "passive"))
      (node (ref "MH4") (pin "3") (pinfunction "V2_3") (pintype "passive"))
      (node (ref "MH4") (pin "4") (pinfunction "V3_4") (pintype "passive"))
      (node (ref "MH4") (pin "5") (pinfunction "V4_5") (pintype "passive"))
      (node (ref "MH4") (pin "6") (pinfunction "V5_6") (pintype "passive"))
      (node (ref "MH4") (pin "7") (pinfunction "V6_7") (pintype "passive"))
      (node (ref "MH5") (pin "1") (pinfunction "MH_1") (pintype "passive"))
      (node (ref "MH5") (pin "2") (pinfunction "V1_2") (pintype "passive"))
      (node (ref "MH5") (pin "3") (pinfunction "V2_3") (pintype "passive"))
      (node (ref "MH5") (pin "4") (pinfunction "V3_4") (pintype "passive"))
      (node (ref "MH5") (pin "5") (pinfunction "V4_5") (pintype "passive"))
      (node (ref "MH5") (pin "6") (pinfunction "V5_6") (pintype "passive"))
      (node (ref "MH5") (pin "7") (pinfunction "V6_7") (pintype "passive"))
      (node (ref "MH6") (pin "1") (pinfunction "MH_1") (pintype "passive"))
      (node (ref "MH6") (pin "2") (pinfunction "V1_2") (pintype "passive"))
      (node (ref "MH6") (pin "3") (pinfunction "V2_3") (pintype "passive"))
      (node (ref "MH6") (pin "4") (pinfunction "V3_4") (pintype "passive"))
      (node (ref "MH6") (pin "5") (pinfunction "V4_5") (pintype "passive"))
      (node (ref "MH6") (pin "6") (pinfunction "V5_6") (pintype "passive"))
      (node (ref "MH6") (pin "7") (pinfunction "V6_7") (pintype "passive"))
      (node (ref "MH7") (pin "1") (pinfunction "MH_1") (pintype "passive"))
      (node (ref "MH7") (pin "2") (pinfunction "V1_2") (pintype "passive"))
      (node (ref "MH7") (pin "3") (pinfunction "V2_3") (pintype "passive"))
      (node (ref "MH7") (pin "4") (pinfunction "V3_4") (pintype "passive"))
      (node (ref "MH7") (pin "5") (pinfunction "V4_5") (pintype "passive"))
      (node (ref "MH7") (pin "6") (pinfunction "V5_6") (pintype "passive"))
      (node (ref "MH7") (pin "7") (pinfunction "V6_7") (pintype "passive"))
      (node (ref "MH8") (pin "1") (pinfunction "MH_1") (pintype "passive"))
      (node (ref "MH8") (pin "2") (pinfunction "V1_2") (pintype "passive"))
      (node (ref "MH8") (pin "3") (pinfunction "V2_3") (pintype "passive"))
      (node (ref "MH8") (pin "4") (pinfunction "V3_4") (pintype "passive"))
      (node (ref "MH8") (pin "5") (pinfunction "V4_5") (pintype "passive"))
      (node (ref "MH8") (pin "6") (pinfunction "V5_6") (pintype "passive"))
      (node (ref "MH8") (pin "7") (pinfunction "V6_7") (pintype "passive"))
      (node (ref "MH9") (pin "1") (pinfunction "MH_1") (pintype "passive"))
      (node (ref "MH9") (pin "2") (pinfunction "V1_2") (pintype "passive"))
      (node (ref "MH9") (pin "3") (pinfunction "V2_3") (pintype "passive"))
      (node (ref "MH9") (pin "4") (pinfunction "V3_4") (pintype "passive"))
      (node (ref "MH9") (pin "5") (pinfunction "V4_5") (pintype "passive"))
      (node (ref "MH9") (pin "6") (pinfunction "V5_6") (pintype "passive"))
      (node (ref "MH9") (pin "7") (pinfunction "V6_7") (pintype "passive"))
      (node (ref "Q1") (pin "2") (pinfunction "S_2") (pintype "passive"))
      (node (ref "Q11") (pin "4") (pinfunction "GND_4") (pintype "passive"))
      (node (ref "Q2") (pin "2") (pinfunction "S_2") (pintype "passive"))
      (node (ref "R4") (pin "2") (pinfunction "2_2") (pintype "passive"))
      (node (ref "R64") (pin "1") (pinfunction "1_1") (pintype "passive"))
      (node (ref "R7") (pin "2") (pinfunction "2_2") (pintype "passive"))
    )
    (net (code "187") (name "INT_VCC") (class "Default")
      (node (ref "F3") (pin "1") (pinfunction "1_1") (pintype "passive"))
      (node (ref "F5") (pin "1") (pinfunction "1_1") (pintype "passive"))
      (node (ref "F6") (pin "1") (pinfunction "1_1") (pintype "passive"))
      (node (ref "F7") (pin "1") (pinfunction "1_1") (pintype "passive"))
    )
    (net (code "188") (name "Net-(F1-Pad1)") (class "Default")
      (node (ref "F1") (pin "1") (pinfunction "1_1") (pintype "passive"))
      (node (ref "J2") (pin "1") (pinfunction "1_1") (pintype "passive"))
    )
    (net (code "189") (name "Net-(F2-Pad1)") (class "Default")
      (node (ref "F2") (pin "1") (pinfunction "1_1") (pintype "passive"))
      (node (ref "J3") (pin "1") (pinfunction "1_1") (pintype "passive"))
    )
    (net (code "190") (name "Net-(F4-Pad1)") (class "Default")
      (node (ref "F4") (pin "1") (pinfunction "1_1") (pintype "passive"))
      (node (ref "J4") (pin "1") (pinfunction "1_1") (pintype "passive"))
    )
    (net (code "191") (name "Net-(J2-Pad2)") (class "Default")
      (node (ref "J2") (pin "2") (pinfunction "2_2") (pintype "passive"))
      (node (ref "R134") (pin "1") (pinfunction "1_1") (pintype "passive"))
    )
    (net (code "192") (name "Net-(J2-Pad4)") (class "Default")
      (node (ref "J2") (pin "4") (pinfunction "4_4") (pintype "passive"))
      (node (ref "R133") (pin "1") (pinfunction "1_1") (pintype "passive"))
    )
    (net (code "193") (name "Net-(J3-Pad2)") (class "Default")
      (node (ref "J3") (pin "2") (pinfunction "2_2") (pintype "passive"))
      (node (ref "R135") (pin "1") (pinfunction "1_1") (pintype "passive"))
    )
    (net (code "194") (name "Net-(J3-Pad4)") (class "Default")
      (node (ref "J3") (pin "4") (pinfunction "4_4") (pintype "passive"))
      (node (ref "R47") (pin "1") (pinfunction "1_1") (pintype "passive"))
    )
    (net (code "195") (name "Net-(J4-Pad2)") (class "Default")
      (node (ref "J4") (pin "2") (pinfunction "2_2") (pintype "passive"))
      (node (ref "R136") (pin "1") (pinfunction "1_1") (pintype "passive"))
    )
    (net (code "196") (name "Net-(J4-Pad4)") (class "Default")
      (node (ref "J4") (pin "4") (pinfunction "4_4") (pintype "passive"))
      (node (ref "R132") (pin "1") (pinfunction "1_1") (pintype "passive"))
    )
    (net (code "197") (name "Net-(J6A-CT0)") (class "Default")
      (node (ref "C1") (pin "1") (pinfunction "1_1") (pintype "passive"))
      (node (ref "J6") (pin "1") (pinfunction "CT2_1") (pintype "passive"))
      (node (ref "J6") (pin "12") (pinfunction "CT0_12") (pintype "passive"))
      (node (ref "J6") (pin "6") (pinfunction "CT1_6") (pintype "passive"))
      (node (ref "J6") (pin "7") (pinfunction "CT3_7") (pintype "passive"))
    )
    (net (code "198") (name "Net-(J6A-LEDG+{slash}LEDO-)") (class "Default")
      (node (ref "J6") (pin "16") (pinfunction "LEDG+/LEDO-_16") (pintype "passive"))
      (node (ref "R8") (pin "2") (pinfunction "2_2") (pintype "passive"))
    )
    (net (code "199") (name "Net-(J6A-LEDY+)") (class "Default")
      (node (ref "J6") (pin "14") (pinfunction "LEDY+_14") (pintype "passive"))
      (node (ref "R9") (pin "2") (pinfunction "2_2") (pintype "passive"))
    )
    (net (code "200") (name "Net-(Q1-G)") (class "Default")
      (node (ref "Q1") (pin "1") (pinfunction "G_1") (pintype "passive"))
      (node (ref "R3") (pin "2") (pinfunction "2_2") (pintype "passive"))
      (node (ref "R4") (pin "1") (pinfunction "1_1") (pintype "passive"))
    )
    (net (code "201") (name "Net-(Q2-G)") (class "Default")
      (node (ref "Q2") (pin "1") (pinfunction "G_1") (pintype "passive"))
      (node (ref "R6") (pin "2") (pinfunction "2_2") (pintype "passive"))
      (node (ref "R7") (pin "1") (pinfunction "1_1") (pintype "passive"))
    )
    (net (code "202") (name "Net-(Q11-EN)") (class "Default")
      (node (ref "Q11") (pin "3") (pinfunction "EN_3") (pintype "passive"))
      (node (ref "R62") (pin "1") (pinfunction "1_1") (pintype "passive"))
      (node (ref "R63") (pin "1") (pinfunction "1_1") (pintype "passive"))
      (node (ref "R64") (pin "2") (pinfunction "2_2") (pintype "passive"))
    )
    (net (code "203") (name "unconnected-(J7-SBU1-PadA8)") (class "Default")
      (node (ref "J7") (pin "A8") (pinfunction "SBU1_A8") (pintype "bidirectional+no_connect"))
    )
    (net (code "204") (name "unconnected-(J7-SBU2-PadB8)") (class "Default")
      (node (ref "J7") (pin "B8") (pinfunction "SBU2_B8") (pintype "bidirectional+no_connect"))
    )
    (net (code "205") (name "unconnected-(J7-VBUS-PadA4_B9)") (class "Default")
      (node (ref "J7") (pin "A4_B9") (pinfunction "VBUS_A4_B9") (pintype "power_in+no_connect"))
    )
    (net (code "206") (name "unconnected-(J7-VBUS-PadB4_A9)") (class "Default")
      (node (ref "J7") (pin "B4_A9") (pinfunction "VBUS_B4_A9") (pintype "power_in+no_connect"))
    )
  )
)
